# jtag.net
KiCad netlist of a schematic drawn in Altium Designer
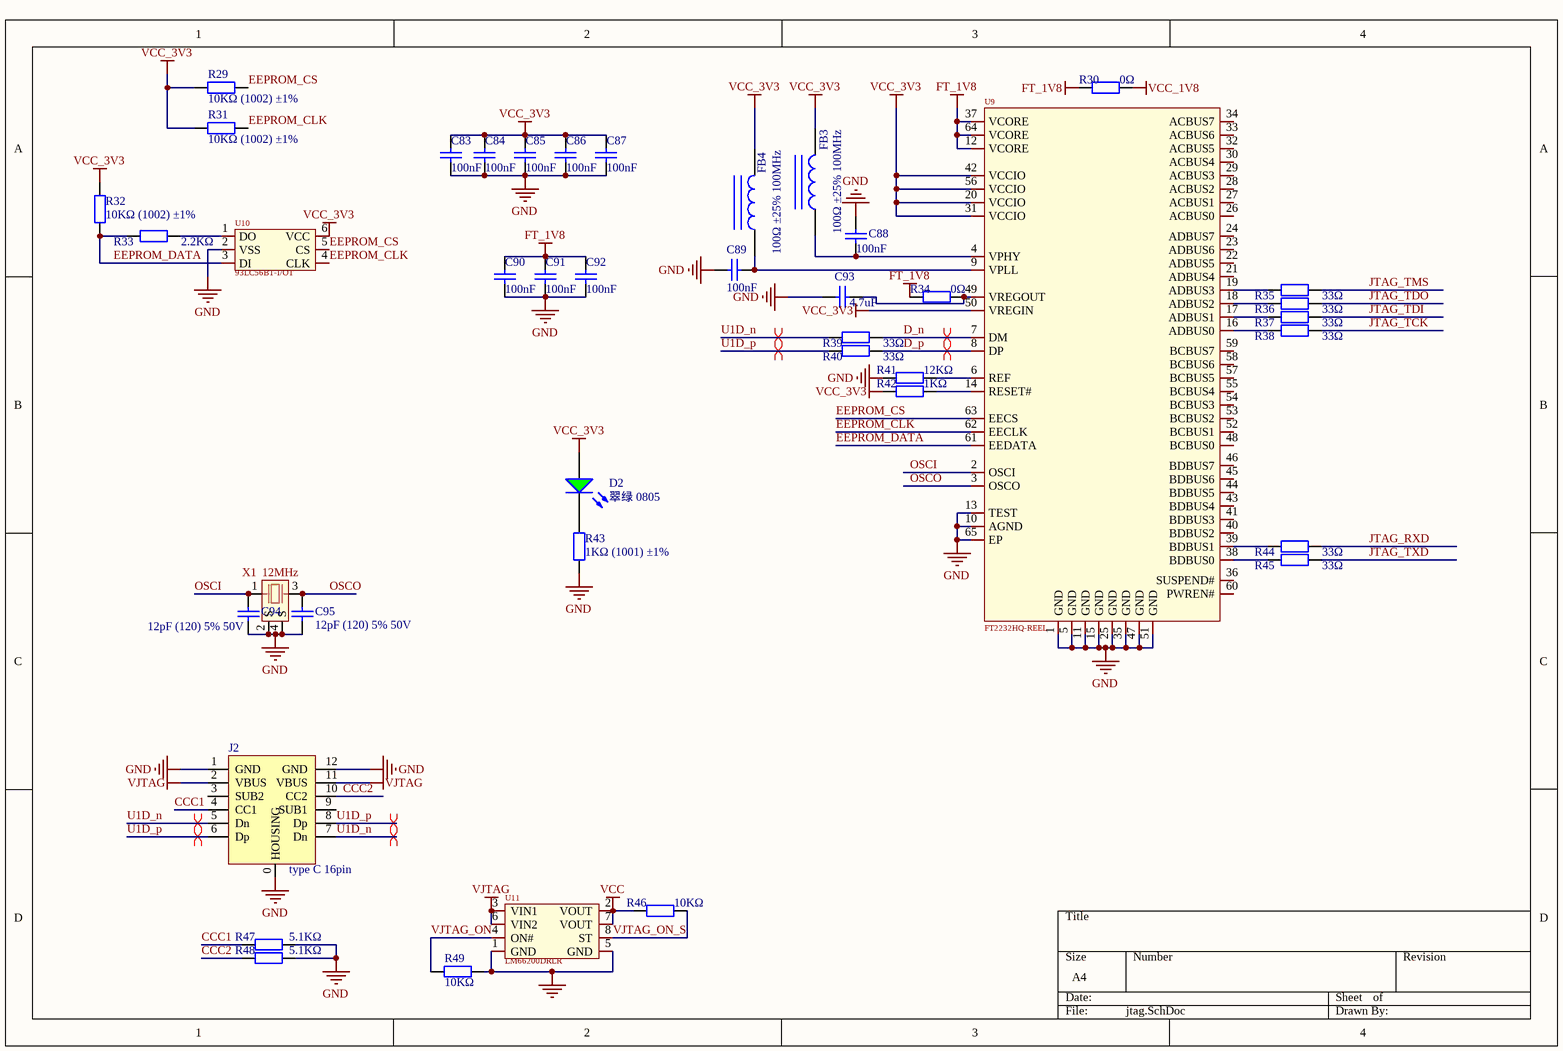
[diagram p0: jtag.SchDoc]

(export (version "E")
  (design (tool "Eeschema 10.0.6"))
  (components
    (comp (ref "C83")
      (value "100nF")
      (footprint "0805_C")
      (description "贴片电容")
      (libsource (lib "Miscellaneous Devices LC") (part "0805 100nF(104) 10% 50V"))
    )
    (comp (ref "C84")
      (value "100nF")
      (footprint "0805_C")
      (description "贴片电容")
      (libsource (lib "Miscellaneous Devices LC") (part "0805 100nF(104) 10% 50V"))
    )
    (comp (ref "C85")
      (value "100nF")
      (footprint "0805_C")
      (description "贴片电容")
      (libsource (lib "Miscellaneous Devices LC") (part "0805 100nF(104) 10% 50V"))
    )
    (comp (ref "C86")
      (value "100nF")
      (footprint "0805_C")
      (description "贴片电容")
      (libsource (lib "Miscellaneous Devices LC") (part "0805 100nF(104) 10% 50V"))
    )
    (comp (ref "C87")
      (value "100nF")
      (footprint "0805_C")
      (description "贴片电容")
      (libsource (lib "Miscellaneous Devices LC") (part "0805 100nF(104) 10% 50V"))
    )
    (comp (ref "C88")
      (value "100nF")
      (footprint "0805_C")
      (description "贴片电容")
      (libsource (lib "Miscellaneous Devices LC") (part "0805 100nF(104) 10% 50V"))
    )
    (comp (ref "C89")
      (value "100nF")
      (footprint "0805_C")
      (description "贴片电容")
      (libsource (lib "Miscellaneous Devices LC") (part "0805 100nF(104) 10% 50V"))
    )
    (comp (ref "C90")
      (value "100nF")
      (footprint "0805_C")
      (description "贴片电容")
      (libsource (lib "Miscellaneous Devices LC") (part "0805 100nF(104) 10% 50V"))
    )
    (comp (ref "C91")
      (value "100nF")
      (footprint "0805_C")
      (description "贴片电容")
      (libsource (lib "Miscellaneous Devices LC") (part "0805 100nF(104) 10% 50V"))
    )
    (comp (ref "C92")
      (value "100nF")
      (footprint "0805_C")
      (description "贴片电容")
      (libsource (lib "Miscellaneous Devices LC") (part "0805 100nF(104) 10% 50V"))
    )
    (comp (ref "C93")
      (value "4.7uF")
      (footprint "0805_C")
      (description "贴片电容")
      (libsource (lib "Miscellaneous Devices LC") (part "0805 4.7uF (475) 10% 25V"))
    )
    (comp (ref "C94")
      (value "12pF (120) 5% 50V")
      (footprint "0805_C")
      (description "贴片电容")
      (libsource (lib "Miscellaneous Devices LC") (part "0805 12pF (120) 5% 50V"))
    )
    (comp (ref "C95")
      (value "12pF (120) 5% 50V")
      (footprint "0805_C")
      (description "贴片电容")
      (libsource (lib "Miscellaneous Devices LC") (part "0805 12pF (120) 5% 50V"))
    )
    (comp (ref "D2")
      (value "翠绿 0805")
      (footprint "0805_LED_S1")
      (description "发光二极管")
      (libsource (lib "Miscellaneous Devices LC") (part "0805 翠绿"))
    )
    (comp (ref "FB3")
      (value "100Ω ±25% 100MHz")
      (footprint "0805_L")
      (description "贴片磁珠")
      (libsource (lib "Miscellaneous Devices LC") (part "0805 100Ω 25% 100MHz"))
    )
    (comp (ref "FB4")
      (value "100Ω ±25% 100MHz")
      (footprint "0805_L")
      (description "贴片磁珠")
      (libsource (lib "Miscellaneous Devices LC") (part "0805 100Ω 25% 100MHz"))
    )
    (comp (ref "J2")
      (value "type C 16pin")
      (footprint "USB type C  16pin")
      (description "16针脚C口")
      (libsource (lib "五向开关") (part "USB type C 16pin"))
    )
    (comp (ref "R29")
      (value "10KΩ (1002) ±1%")
      (footprint "0805_R")
      (description "贴片电阻")
      (libsource (lib "Miscellaneous Devices LC") (part "0805 10KΩ (1002) 1%"))
    )
    (comp (ref "R30")
      (value "0Ω")
      (footprint "0402_R")
      (description "贴片电阻")
      (libsource (lib "Miscellaneous Devices LC") (part "0402 0Ω (0R0) 1%"))
    )
    (comp (ref "R31")
      (value "10KΩ (1002) ±1%")
      (footprint "0805_R")
      (description "贴片电阻")
      (libsource (lib "Miscellaneous Devices LC") (part "0805 10KΩ (1002) 1%"))
    )
    (comp (ref "R32")
      (value "10KΩ (1002) ±1%")
      (footprint "0805_R")
      (description "贴片电阻")
      (libsource (lib "") (part "0805 10KΩ (1002) 1%_1"))
    )
    (comp (ref "R33")
      (value "2.2KΩ")
      (footprint "0805_R")
      (description "贴片电阻")
      (libsource (lib "Miscellaneous Devices LC") (part "0805 2.2KΩ (2201) 1%"))
    )
    (comp (ref "R34")
      (value "0Ω")
      (footprint "0402_R")
      (description "贴片电阻")
      (libsource (lib "Miscellaneous Devices LC") (part "0402 0Ω (0R0) 1%"))
    )
    (comp (ref "R35")
      (value "33Ω")
      (footprint "0402_R")
      (description "贴片电阻")
      (libsource (lib "Miscellaneous Devices LC") (part "0805 33Ω (33R0) 1%"))
    )
    (comp (ref "R36")
      (value "33Ω")
      (footprint "0402_R")
      (description "贴片电阻")
      (libsource (lib "Miscellaneous Devices LC") (part "0805 33Ω (33R0) 1%"))
    )
    (comp (ref "R37")
      (value "33Ω")
      (footprint "0402_R")
      (description "贴片电阻")
      (libsource (lib "Miscellaneous Devices LC") (part "0805 33Ω (33R0) 1%"))
    )
    (comp (ref "R38")
      (value "33Ω")
      (footprint "0402_R")
      (description "贴片电阻")
      (libsource (lib "Miscellaneous Devices LC") (part "0805 33Ω (33R0) 1%"))
    )
    (comp (ref "R39")
      (value "33Ω")
      (footprint "0402_R")
      (description "贴片电阻")
      (libsource (lib "Miscellaneous Devices LC") (part "0805 33Ω (33R0) 1%"))
    )
    (comp (ref "R40")
      (value "33Ω")
      (footprint "0402_R")
      (description "贴片电阻")
      (libsource (lib "Miscellaneous Devices LC") (part "0805 33Ω (33R0) 1%"))
    )
    (comp (ref "R41")
      (value "12KΩ")
      (footprint "0805_R")
      (description "贴片电阻")
      (libsource (lib "Miscellaneous Devices LC") (part "0805 12KΩ (1202) 1%"))
    )
    (comp (ref "R42")
      (value "1KΩ")
      (footprint "0805_R")
      (description "贴片电阻")
      (libsource (lib "") (part "0805 1KΩ (1001) 1%_1"))
    )
    (comp (ref "R43")
      (value "1KΩ (1001) ±1%")
      (footprint "0805_R")
      (description "贴片电阻")
      (libsource (lib "Miscellaneous Devices LC") (part "0805 1KΩ (1001) 1%"))
    )
    (comp (ref "R44")
      (value "33Ω")
      (footprint "0402_R")
      (description "贴片电阻")
      (libsource (lib "Miscellaneous Devices LC") (part "0805 33Ω (33R0) 1%"))
    )
    (comp (ref "R45")
      (value "33Ω")
      (footprint "0402_R")
      (description "贴片电阻")
      (libsource (lib "Miscellaneous Devices LC") (part "0805 33Ω (33R0) 1%"))
    )
    (comp (ref "R46")
      (value "10KΩ")
      (footprint "0805_R")
      (description "贴片电阻")
      (libsource (lib "") (part "0805 10KΩ (1002) 1%_2"))
    )
    (comp (ref "R47")
      (value "5.1KΩ")
      (footprint "0805_R")
      (description "贴片电阻")
      (libsource (lib "Miscellaneous Devices LC") (part "0402 5.1KΩ (5101) 1%"))
    )
    (comp (ref "R48")
      (value "5.1KΩ")
      (footprint "0805_R")
      (description "贴片电阻")
      (libsource (lib "Miscellaneous Devices LC") (part "0402 5.1KΩ (5101) 1%"))
    )
    (comp (ref "R49")
      (value "10KΩ")
      (footprint "0805_R")
      (description "贴片电阻")
      (libsource (lib "Miscellaneous Devices LC") (part "0805 10KΩ (1002) 1%"))
    )
    (comp (ref "U9")
      (value "FT2232HQ-REEL")
      (footprint "QFN-64_L9.0-W9.0-P0.50-TL-EP4.3")
      (fields (field (name "MANUFACTURER") "FTDI(飞特帝亚)"))
      (libsource (lib "五向开关") (part "FT2232HQ-REEL"))
    )
    (comp (ref "U10")
      (value "93LC56BT-I/OT")
      (footprint "SOT-23-6_L2.9-W1.6-P0.95-LS2.8-BR")
      (fields (field (name "MANUFACTURER") "MICROCHIP(美国微芯)"))
      (libsource (lib "五向开关") (part "93LC56BT-I/OT"))
    )
    (comp (ref "U11")
      (value "LM66200DRLR")
      (footprint "SOT-583-8_L2.1-W1.2-P0.50-LS1.6-BL")
      (description "理想二极管")
      (fields (field (name "MANUFACTURER") "TI(德州仪器)"))
      (libsource (lib "五向开关") (part "LM66200DRLR"))
    )
    (comp (ref "X1")
      (value "12MHz")
      (footprint "3225")
      (description "4脚贴片无源晶体")
      (fields (field (name "MANUFACTURER") "YJX(雅晶鑫)") (field (name "MANUFACTURER PART") "TAXM8M4RDBCCT2T"))
      (libsource (lib "五向开关") (part "四脚无源晶体"))
    )
  )
  (nets
    (net (code "1") (name "/CCC1") (class "Default")
      (node (ref "J2") (pin "4") (pinfunction "CC1_4") (pintype "passive"))
      (node (ref "R47") (pin "1") (pinfunction "1_1") (pintype "passive"))
    )
    (net (code "2") (name "/CCC2") (class "Default")
      (node (ref "J2") (pin "10") (pinfunction "CC2_10") (pintype "passive"))
      (node (ref "R48") (pin "1") (pinfunction "1_1") (pintype "passive"))
    )
    (net (code "3") (name "/D_n") (class "Default")
      (node (ref "R39") (pin "2") (pinfunction "2_2") (pintype "passive"))
      (node (ref "U9") (pin "7") (pinfunction "DM_7") (pintype "passive"))
    )
    (net (code "4") (name "/D_p") (class "Default")
      (node (ref "R40") (pin "2") (pinfunction "2_2") (pintype "passive"))
      (node (ref "U9") (pin "8") (pinfunction "DP_8") (pintype "passive"))
    )
    (net (code "5") (name "/EEPROM_CLK") (class "Default")
      (node (ref "R31") (pin "1") (pinfunction "1_1") (pintype "passive"))
      (node (ref "U10") (pin "4") (pinfunction "CLK_4") (pintype "passive"))
      (node (ref "U9") (pin "62") (pinfunction "EECLK_62") (pintype "passive"))
    )
    (net (code "6") (name "/EEPROM_CS") (class "Default")
      (node (ref "R29") (pin "1") (pinfunction "1_1") (pintype "passive"))
      (node (ref "U10") (pin "5") (pinfunction "CS_5") (pintype "passive"))
      (node (ref "U9") (pin "63") (pinfunction "EECS_63") (pintype "passive"))
    )
    (net (code "7") (name "/EEPROM_DATA") (class "Default")
      (node (ref "R32") (pin "1") (pinfunction "1_1") (pintype "passive"))
      (node (ref "R33") (pin "1") (pinfunction "1_1") (pintype "passive"))
      (node (ref "U10") (pin "3") (pinfunction "DI_3") (pintype "passive"))
      (node (ref "U9") (pin "61") (pinfunction "EEDATA_61") (pintype "passive"))
    )
    (net (code "8") (name "/JTAG_RXD") (class "Default")
      (node (ref "R44") (pin "2") (pinfunction "2_2") (pintype "passive"))
    )
    (net (code "9") (name "/JTAG_TCK") (class "Default")
      (node (ref "R38") (pin "2") (pinfunction "2_2") (pintype "passive"))
    )
    (net (code "10") (name "/JTAG_TDI") (class "Default")
      (node (ref "R37") (pin "2") (pinfunction "2_2") (pintype "passive"))
    )
    (net (code "11") (name "/JTAG_TDO") (class "Default")
      (node (ref "R36") (pin "2") (pinfunction "2_2") (pintype "passive"))
    )
    (net (code "12") (name "/JTAG_TMS") (class "Default")
      (node (ref "R35") (pin "2") (pinfunction "2_2") (pintype "passive"))
    )
    (net (code "13") (name "/JTAG_TXD") (class "Default")
      (node (ref "R45") (pin "2") (pinfunction "2_2") (pintype "passive"))
    )
    (net (code "14") (name "/OSCI") (class "Default")
      (node (ref "C94") (pin "2") (pinfunction "2_2") (pintype "passive"))
      (node (ref "U9") (pin "2") (pinfunction "OSCI_2") (pintype "passive"))
      (node (ref "X1") (pin "1") (pintype "passive"))
    )
    (net (code "15") (name "/OSCO") (class "Default")
      (node (ref "C95") (pin "2") (pinfunction "2_2") (pintype "passive"))
      (node (ref "U9") (pin "3") (pinfunction "OSCO_3") (pintype "passive"))
      (node (ref "X1") (pin "3") (pintype "passive"))
    )
    (net (code "16") (name "/U1D_n") (class "Default")
      (node (ref "J2") (pin "5") (pinfunction "Dn_5") (pintype "passive"))
      (node (ref "J2") (pin "7") (pinfunction "Dn_7") (pintype "passive"))
      (node (ref "R39") (pin "1") (pinfunction "1_1") (pintype "passive"))
    )
    (net (code "17") (name "/U1D_p") (class "Default")
      (node (ref "J2") (pin "6") (pinfunction "Dp_6") (pintype "passive"))
      (node (ref "J2") (pin "8") (pinfunction "Dp_8") (pintype "passive"))
      (node (ref "R40") (pin "1") (pinfunction "1_1") (pintype "passive"))
    )
    (net (code "18") (name "/VJTAG_ON") (class "Default")
      (node (ref "R49") (pin "2") (pinfunction "2_2") (pintype "passive"))
      (node (ref "U11") (pin "4") (pinfunction "ON#_4") (pintype "passive"))
    )
    (net (code "19") (name "/VJTAG_ON_S") (class "Default")
      (node (ref "R46") (pin "2") (pinfunction "2_2") (pintype "passive"))
      (node (ref "U11") (pin "8") (pinfunction "ST_8") (pintype "passive"))
    )
    (net (code "20") (name "FT_1V8") (class "Default")
      (node (ref "C90") (pin "2") (pinfunction "2_2") (pintype "passive"))
      (node (ref "C91") (pin "2") (pinfunction "2_2") (pintype "passive"))
      (node (ref "C92") (pin "2") (pinfunction "2_2") (pintype "passive"))
      (node (ref "R30") (pin "1") (pinfunction "1_1") (pintype "passive"))
      (node (ref "R34") (pin "1") (pinfunction "1_1") (pintype "passive"))
      (node (ref "U9") (pin "12") (pinfunction "VCORE_12") (pintype "passive"))
      (node (ref "U9") (pin "37") (pinfunction "VCORE_37") (pintype "passive"))
      (node (ref "U9") (pin "64") (pinfunction "VCORE_64") (pintype "passive"))
    )
    (net (code "21") (name "GND") (class "Default")
      (node (ref "C83") (pin "1") (pinfunction "1_1") (pintype "passive"))
      (node (ref "C84") (pin "1") (pinfunction "1_1") (pintype "passive"))
      (node (ref "C85") (pin "1") (pinfunction "1_1") (pintype "passive"))
      (node (ref "C86") (pin "1") (pinfunction "1_1") (pintype "passive"))
      (node (ref "C87") (pin "1") (pinfunction "1_1") (pintype "passive"))
      (node (ref "C88") (pin "2") (pinfunction "2_2") (pintype "passive"))
      (node (ref "C89") (pin "2") (pinfunction "2_2") (pintype "passive"))
      (node (ref "C90") (pin "1") (pinfunction "1_1") (pintype "passive"))
      (node (ref "C91") (pin "1") (pinfunction "1_1") (pintype "passive"))
      (node (ref "C92") (pin "1") (pinfunction "1_1") (pintype "passive"))
      (node (ref "C93") (pin "1") (pinfunction "1_1") (pintype "passive"))
      (node (ref "C94") (pin "1") (pinfunction "1_1") (pintype "passive"))
      (node (ref "C95") (pin "1") (pinfunction "1_1") (pintype "passive"))
      (node (ref "J2") (pin "0") (pinfunction "HOUSING_0") (pintype "passive"))
      (node (ref "J2") (pin "1") (pinfunction "GND_1") (pintype "passive"))
      (node (ref "J2") (pin "12") (pinfunction "GND_12") (pintype "passive"))
      (node (ref "R41") (pin "1") (pinfunction "1_1") (pintype "passive"))
      (node (ref "R43") (pin "1") (pinfunction "1_1") (pintype "passive"))
      (node (ref "R47") (pin "2") (pinfunction "2_2") (pintype "passive"))
      (node (ref "R48") (pin "2") (pinfunction "2_2") (pintype "passive"))
      (node (ref "R49") (pin "1") (pinfunction "1_1") (pintype "passive"))
      (node (ref "U10") (pin "2") (pinfunction "VSS_2") (pintype "passive"))
      (node (ref "U11") (pin "1") (pinfunction "GND_1") (pintype "passive"))
      (node (ref "U11") (pin "5") (pinfunction "GND_5") (pintype "passive"))
      (node (ref "U9") (pin "1") (pinfunction "GND_1") (pintype "passive"))
      (node (ref "U9") (pin "10") (pinfunction "AGND_10") (pintype "passive"))
      (node (ref "U9") (pin "11") (pinfunction "GND_11") (pintype "passive"))
      (node (ref "U9") (pin "13") (pinfunction "TEST_13") (pintype "passive"))
      (node (ref "U9") (pin "15") (pinfunction "GND_15") (pintype "passive"))
      (node (ref "U9") (pin "25") (pinfunction "GND_25") (pintype "passive"))
      (node (ref "U9") (pin "35") (pinfunction "GND_35") (pintype "passive"))
      (node (ref "U9") (pin "47") (pinfunction "GND_47") (pintype "passive"))
      (node (ref "U9") (pin "5") (pinfunction "GND_5") (pintype "passive"))
      (node (ref "U9") (pin "51") (pinfunction "GND_51") (pintype "passive"))
      (node (ref "U9") (pin "65") (pinfunction "EP_65") (pintype "passive"))
      (node (ref "X1") (pin "2") (pinfunction "S_2") (pintype "passive"))
      (node (ref "X1") (pin "4") (pinfunction "S_4") (pintype "passive"))
    )
    (net (code "22") (name "Net-(D2-PadK)") (class "Default")
      (node (ref "D2") (pin "K") (pinfunction "K_K") (pintype "passive"))
      (node (ref "R43") (pin "2") (pinfunction "2_2") (pintype "passive"))
    )
    (net (code "23") (name "Net-(U9-ADBUS0)") (class "Default")
      (node (ref "R38") (pin "1") (pinfunction "1_1") (pintype "passive"))
      (node (ref "U9") (pin "16") (pinfunction "ADBUS0_16") (pintype "passive"))
    )
    (net (code "24") (name "Net-(U9-ADBUS1)") (class "Default")
      (node (ref "R37") (pin "1") (pinfunction "1_1") (pintype "passive"))
      (node (ref "U9") (pin "17") (pinfunction "ADBUS1_17") (pintype "passive"))
    )
    (net (code "25") (name "Net-(U9-ADBUS2)") (class "Default")
      (node (ref "R36") (pin "1") (pinfunction "1_1") (pintype "passive"))
      (node (ref "U9") (pin "18") (pinfunction "ADBUS2_18") (pintype "passive"))
    )
    (net (code "26") (name "Net-(U9-ADBUS3)") (class "Default")
      (node (ref "R35") (pin "1") (pinfunction "1_1") (pintype "passive"))
      (node (ref "U9") (pin "19") (pinfunction "ADBUS3_19") (pintype "passive"))
    )
    (net (code "27") (name "Net-(U9-BDBUS0)") (class "Default")
      (node (ref "R45") (pin "1") (pinfunction "1_1") (pintype "passive"))
      (node (ref "U9") (pin "38") (pinfunction "BDBUS0_38") (pintype "passive"))
    )
    (net (code "28") (name "Net-(U9-BDBUS1)") (class "Default")
      (node (ref "R44") (pin "1") (pinfunction "1_1") (pintype "passive"))
      (node (ref "U9") (pin "39") (pinfunction "BDBUS1_39") (pintype "passive"))
    )
    (net (code "29") (name "Net-(U9-REF)") (class "Default")
      (node (ref "R41") (pin "2") (pinfunction "2_2") (pintype "passive"))
      (node (ref "U9") (pin "6") (pinfunction "REF_6") (pintype "passive"))
    )
    (net (code "30") (name "Net-(U9-RESET#)") (class "Default")
      (node (ref "R42") (pin "2") (pinfunction "2_2") (pintype "passive"))
      (node (ref "U9") (pin "14") (pinfunction "RESET#_14") (pintype "passive"))
    )
    (net (code "31") (name "Net-(U9-VPHY)") (class "Default")
      (node (ref "C88") (pin "1") (pinfunction "1_1") (pintype "passive"))
      (node (ref "FB3") (pin "1") (pinfunction "1_1") (pintype "passive"))
      (node (ref "U9") (pin "4") (pinfunction "VPHY_4") (pintype "passive"))
    )
    (net (code "32") (name "Net-(U9-VPLL)") (class "Default")
      (node (ref "C89") (pin "1") (pinfunction "1_1") (pintype "passive"))
      (node (ref "FB4") (pin "1") (pinfunction "1_1") (pintype "passive"))
      (node (ref "U9") (pin "9") (pinfunction "VPLL_9") (pintype "passive"))
    )
    (net (code "33") (name "Net-(U9-VREGOUT)") (class "Default")
      (node (ref "C93") (pin "2") (pinfunction "2_2") (pintype "passive"))
      (node (ref "R34") (pin "2") (pinfunction "2_2") (pintype "passive"))
      (node (ref "U9") (pin "49") (pinfunction "VREGOUT_49") (pintype "passive"))
    )
    (net (code "34") (name "Net-(U10-DO)") (class "Default")
      (node (ref "R33") (pin "2") (pinfunction "2_2") (pintype "passive"))
      (node (ref "U10") (pin "1") (pinfunction "DO_1") (pintype "passive"))
    )
    (net (code "35") (name "VCC") (class "Default")
      (node (ref "R46") (pin "1") (pinfunction "1_1") (pintype "passive"))
      (node (ref "U11") (pin "2") (pinfunction "VOUT_2") (pintype "passive"))
      (node (ref "U11") (pin "7") (pinfunction "VOUT_7") (pintype "passive"))
    )
    (net (code "36") (name "VCC_1V8") (class "Default")
      (node (ref "R30") (pin "2") (pinfunction "2_2") (pintype "passive"))
    )
    (net (code "37") (name "VCC_3V3") (class "Default")
      (node (ref "C83") (pin "2") (pinfunction "2_2") (pintype "passive"))
      (node (ref "C84") (pin "2") (pinfunction "2_2") (pintype "passive"))
      (node (ref "C85") (pin "2") (pinfunction "2_2") (pintype "passive"))
      (node (ref "C86") (pin "2") (pinfunction "2_2") (pintype "passive"))
      (node (ref "C87") (pin "2") (pinfunction "2_2") (pintype "passive"))
      (node (ref "D2") (pin "A") (pinfunction "A_A") (pintype "passive"))
      (node (ref "FB3") (pin "2") (pinfunction "2_2") (pintype "passive"))
      (node (ref "FB4") (pin "2") (pinfunction "2_2") (pintype "passive"))
      (node (ref "R29") (pin "2") (pinfunction "2_2") (pintype "passive"))
      (node (ref "R31") (pin "2") (pinfunction "2_2") (pintype "passive"))
      (node (ref "R32") (pin "2") (pinfunction "2_2") (pintype "passive"))
      (node (ref "R42") (pin "1") (pinfunction "1_1") (pintype "passive"))
      (node (ref "U10") (pin "6") (pinfunction "VCC_6") (pintype "passive"))
      (node (ref "U9") (pin "20") (pinfunction "VCCIO_20") (pintype "passive"))
      (node (ref "U9") (pin "31") (pinfunction "VCCIO_31") (pintype "passive"))
      (node (ref "U9") (pin "42") (pinfunction "VCCIO_42") (pintype "passive"))
      (node (ref "U9") (pin "50") (pinfunction "VREGIN_50") (pintype "passive"))
      (node (ref "U9") (pin "56") (pinfunction "VCCIO_56") (pintype "passive"))
    )
    (net (code "38") (name "VJTAG") (class "Default")
      (node (ref "J2") (pin "11") (pinfunction "VBUS_11") (pintype "passive"))
      (node (ref "J2") (pin "2") (pinfunction "VBUS_2") (pintype "passive"))
      (node (ref "U11") (pin "3") (pinfunction "VIN1_3") (pintype "passive"))
      (node (ref "U11") (pin "6") (pinfunction "VIN2_6") (pintype "passive"))
    )
    (net (code "39") (name "unconnected-(J2-SUB1-Pad9)") (class "Default")
      (node (ref "J2") (pin "9") (pinfunction "SUB1_9") (pintype "passive"))
    )
    (net (code "40") (name "unconnected-(J2-SUB2-Pad3)") (class "Default")
      (node (ref "J2") (pin "3") (pinfunction "SUB2_3") (pintype "passive"))
    )
    (net (code "41") (name "unconnected-(U9-ACBUS0-Pad26)") (class "Default")
      (node (ref "U9") (pin "26") (pinfunction "ACBUS0_26") (pintype "passive"))
    )
    (net (code "42") (name "unconnected-(U9-ACBUS1-Pad27)") (class "Default")
      (node (ref "U9") (pin "27") (pinfunction "ACBUS1_27") (pintype "passive"))
    )
    (net (code "43") (name "unconnected-(U9-ACBUS2-Pad28)") (class "Default")
      (node (ref "U9") (pin "28") (pinfunction "ACBUS2_28") (pintype "passive"))
    )
    (net (code "44") (name "unconnected-(U9-ACBUS3-Pad29)") (class "Default")
      (node (ref "U9") (pin "29") (pinfunction "ACBUS3_29") (pintype "passive"))
    )
    (net (code "45") (name "unconnected-(U9-ACBUS4-Pad30)") (class "Default")
      (node (ref "U9") (pin "30") (pinfunction "ACBUS4_30") (pintype "passive"))
    )
    (net (code "46") (name "unconnected-(U9-ACBUS5-Pad32)") (class "Default")
      (node (ref "U9") (pin "32") (pinfunction "ACBUS5_32") (pintype "passive"))
    )
    (net (code "47") (name "unconnected-(U9-ACBUS6-Pad33)") (class "Default")
      (node (ref "U9") (pin "33") (pinfunction "ACBUS6_33") (pintype "passive"))
    )
    (net (code "48") (name "unconnected-(U9-ACBUS7-Pad34)") (class "Default")
      (node (ref "U9") (pin "34") (pinfunction "ACBUS7_34") (pintype "passive"))
    )
    (net (code "49") (name "unconnected-(U9-ADBUS4-Pad21)") (class "Default")
      (node (ref "U9") (pin "21") (pinfunction "ADBUS4_21") (pintype "passive"))
    )
    (net (code "50") (name "unconnected-(U9-ADBUS5-Pad22)") (class "Default")
      (node (ref "U9") (pin "22") (pinfunction "ADBUS5_22") (pintype "passive"))
    )
    (net (code "51") (name "unconnected-(U9-ADBUS6-Pad23)") (class "Default")
      (node (ref "U9") (pin "23") (pinfunction "ADBUS6_23") (pintype "passive"))
    )
    (net (code "52") (name "unconnected-(U9-ADBUS7-Pad24)") (class "Default")
      (node (ref "U9") (pin "24") (pinfunction "ADBUS7_24") (pintype "passive"))
    )
    (net (code "53") (name "unconnected-(U9-BCBUS0-Pad48)") (class "Default")
      (node (ref "U9") (pin "48") (pinfunction "BCBUS0_48") (pintype "passive"))
    )
    (net (code "54") (name "unconnected-(U9-BCBUS1-Pad52)") (class "Default")
      (node (ref "U9") (pin "52") (pinfunction "BCBUS1_52") (pintype "passive"))
    )
    (net (code "55") (name "unconnected-(U9-BCBUS2-Pad53)") (class "Default")
      (node (ref "U9") (pin "53") (pinfunction "BCBUS2_53") (pintype "passive"))
    )
    (net (code "56") (name "unconnected-(U9-BCBUS3-Pad54)") (class "Default")
      (node (ref "U9") (pin "54") (pinfunction "BCBUS3_54") (pintype "passive"))
    )
    (net (code "57") (name "unconnected-(U9-BCBUS4-Pad55)") (class "Default")
      (node (ref "U9") (pin "55") (pinfunction "BCBUS4_55") (pintype "passive"))
    )
    (net (code "58") (name "unconnected-(U9-BCBUS5-Pad57)") (class "Default")
      (node (ref "U9") (pin "57") (pinfunction "BCBUS5_57") (pintype "passive"))
    )
    (net (code "59") (name "unconnected-(U9-BCBUS6-Pad58)") (class "Default")
      (node (ref "U9") (pin "58") (pinfunction "BCBUS6_58") (pintype "passive"))
    )
    (net (code "60") (name "unconnected-(U9-BCBUS7-Pad59)") (class "Default")
      (node (ref "U9") (pin "59") (pinfunction "BCBUS7_59") (pintype "passive"))
    )
    (net (code "61") (name "unconnected-(U9-BDBUS2-Pad40)") (class "Default")
      (node (ref "U9") (pin "40") (pinfunction "BDBUS2_40") (pintype "passive"))
    )
    (net (code "62") (name "unconnected-(U9-BDBUS3-Pad41)") (class "Default")
      (node (ref "U9") (pin "41") (pinfunction "BDBUS3_41") (pintype "passive"))
    )
    (net (code "63") (name "unconnected-(U9-BDBUS4-Pad43)") (class "Default")
      (node (ref "U9") (pin "43") (pinfunction "BDBUS4_43") (pintype "passive"))
    )
    (net (code "64") (name "unconnected-(U9-BDBUS5-Pad44)") (class "Default")
      (node (ref "U9") (pin "44") (pinfunction "BDBUS5_44") (pintype "passive"))
    )
    (net (code "65") (name "unconnected-(U9-BDBUS6-Pad45)") (class "Default")
      (node (ref "U9") (pin "45") (pinfunction "BDBUS6_45") (pintype "passive"))
    )
    (net (code "66") (name "unconnected-(U9-BDBUS7-Pad46)") (class "Default")
      (node (ref "U9") (pin "46") (pinfunction "BDBUS7_46") (pintype "passive"))
    )
    (net (code "67") (name "unconnected-(U9-PWREN#-Pad60)") (class "Default")
      (node (ref "U9") (pin "60") (pinfunction "PWREN#_60") (pintype "passive"))
    )
    (net (code "68") (name "unconnected-(U9-SUSPEND#-Pad36)") (class "Default")
      (node (ref "U9") (pin "36") (pinfunction "SUSPEND#_36") (pintype "passive"))
    )
  )
)
